# C128_U36_1MB_V2.net
KiCad netlist of a schematic drawn in EAGLE
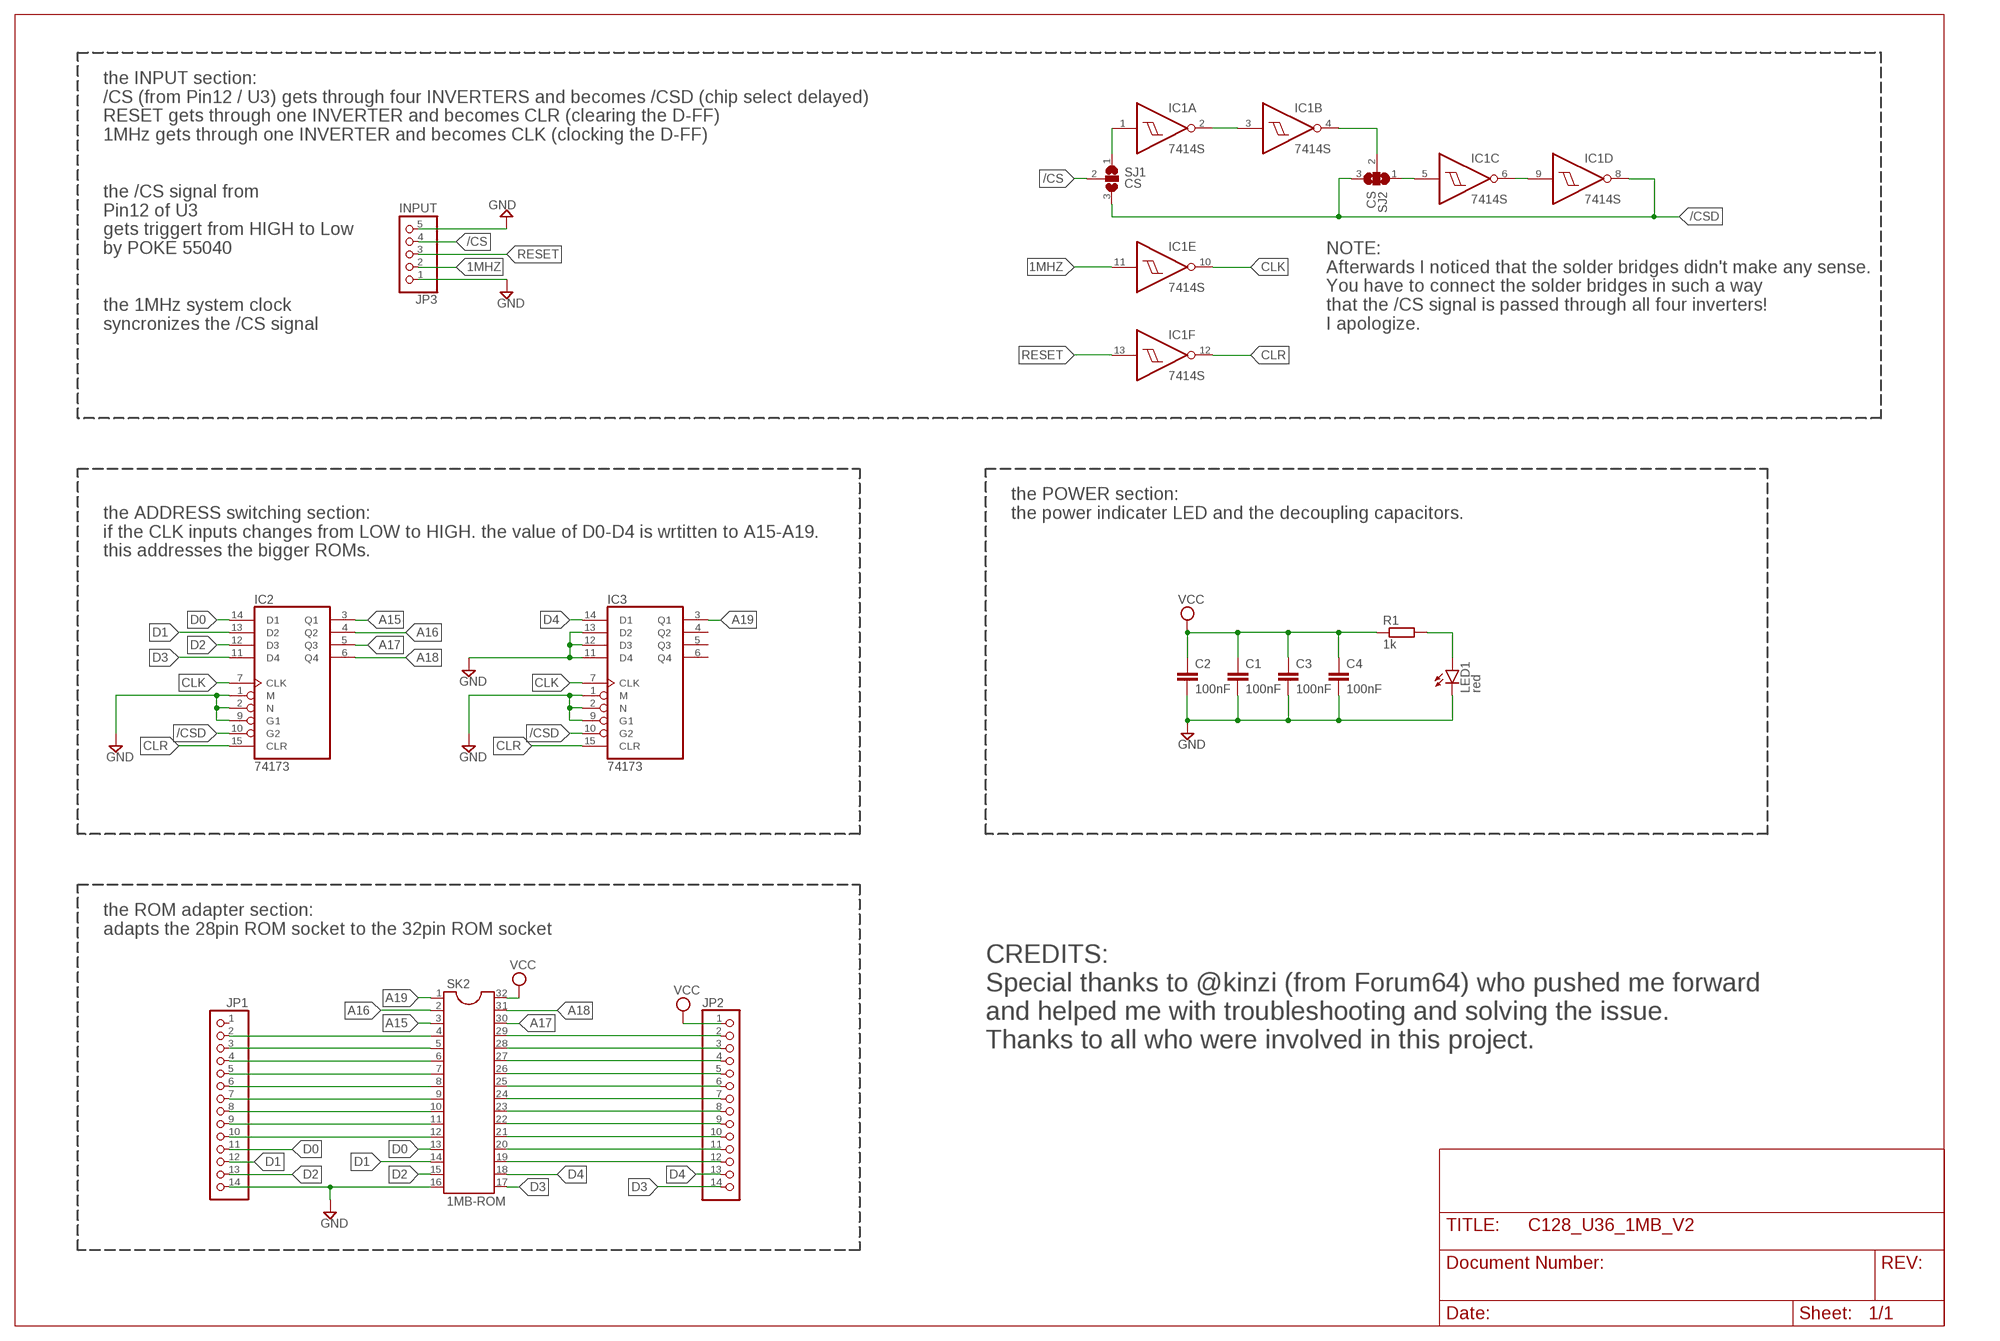
[diagram p0: schematic, sheet 1]

(export (version "E")
  (design (tool "Eeschema 10.0.6"))
  (components
    (comp (ref "C1")
      (value "100nF")
      (footprint "eagle-import:C0603K")
      (libsource (lib "eagle-import") (part "C-EUC0603K"))
    )
    (comp (ref "C2")
      (value "100nF")
      (footprint "eagle-import:C0603K")
      (libsource (lib "eagle-import") (part "C-EUC0603K"))
    )
    (comp (ref "C3")
      (value "100nF")
      (footprint "eagle-import:C0603K")
      (libsource (lib "eagle-import") (part "C-EUC0603K"))
    )
    (comp (ref "C4")
      (value "100nF")
      (footprint "eagle-import:C0603K")
      (libsource (lib "eagle-import") (part "C-EUC0603K"))
    )
    (comp (ref "IC1")
      (value "7414S")
      (footprint "eagle-import:SO14_DET")
      (libsource (lib "eagle-import") (part "7414SMALL"))
    )
    (comp (ref "IC2")
      (value "74173")
      (footprint "eagle-import:SO16_DET")
      (libsource (lib "eagle-import") (part "74173"))
    )
    (comp (ref "IC3")
      (value "74173")
      (footprint "eagle-import:SO16_DET")
      (fields (field (name "SPICEPREFIX") "X"))
      (libsource (lib "eagle-import") (part "74173"))
    )
    (comp (ref "JP1")
      (value "PINHD-1X14")
      (footprint "eagle-import:1X14")
      (libsource (lib "eagle-import") (part "PINHD-1X14"))
    )
    (comp (ref "JP2")
      (value "PINHD-1X14")
      (footprint "eagle-import:1X14")
      (libsource (lib "eagle-import") (part "PINHD-1X14"))
    )
    (comp (ref "JP3")
      (value "INPUT")
      (footprint "eagle-import:1X05_90")
      (libsource (lib "eagle-import") (part "PINHD-1X5/90"))
    )
    (comp (ref "LED1")
      (value "red")
      (footprint "eagle-import:CHIPLED_0603")
      (libsource (lib "eagle-import") (part "LEDCHIPLED_0603"))
    )
    (comp (ref "R1")
      (value "1k")
      (footprint "eagle-import:R0603")
      (libsource (lib "eagle-import") (part "R-EU_R0603"))
    )
    (comp (ref "SJ1")
      (value "CS")
      (footprint "eagle-import:SJ_2")
      (libsource (lib "eagle-import") (part "SJ2W"))
    )
    (comp (ref "SJ2")
      (value "CS")
      (footprint "eagle-import:SJ_2")
      (libsource (lib "eagle-import") (part "SJ2W"))
    )
    (comp (ref "SK2")
      (value "1MB-ROM")
      (footprint "eagle-import:DIL32")
      (libsource (lib "eagle-import") (part "DIL32"))
    )
  )
  (nets
    (net (code "1") (name "1MHZ") (class "Default")
      (node (ref "IC1") (pin "11") (pinfunction "I_11") (pintype "input"))
      (node (ref "JP3") (pin "2") (pinfunction "2_2") (pintype "passive"))
    )
    (net (code "2") (name "A15") (class "Default")
      (node (ref "IC2") (pin "3") (pinfunction "Q1_3") (pintype "tri_state"))
      (node (ref "SK2") (pin "3") (pinfunction "3_3") (pintype "passive"))
    )
    (net (code "3") (name "A16") (class "Default")
      (node (ref "IC2") (pin "4") (pinfunction "Q2_4") (pintype "tri_state"))
      (node (ref "SK2") (pin "2") (pinfunction "2_2") (pintype "passive"))
    )
    (net (code "4") (name "A17") (class "Default")
      (node (ref "IC2") (pin "5") (pinfunction "Q3_5") (pintype "tri_state"))
      (node (ref "SK2") (pin "30") (pinfunction "30_30") (pintype "passive"))
    )
    (net (code "5") (name "A18") (class "Default")
      (node (ref "IC2") (pin "6") (pinfunction "Q4_6") (pintype "tri_state"))
      (node (ref "SK2") (pin "31") (pinfunction "31_31") (pintype "passive"))
    )
    (net (code "6") (name "A19") (class "Default")
      (node (ref "IC3") (pin "3") (pinfunction "Q1_3") (pintype "tri_state"))
      (node (ref "SK2") (pin "1") (pinfunction "1_1") (pintype "passive"))
    )
    (net (code "7") (name "CLK") (class "Default")
      (node (ref "IC1") (pin "10") (pinfunction "O_10") (pintype "output"))
      (node (ref "IC2") (pin "7") (pinfunction "CLK_7") (pintype "input"))
      (node (ref "IC3") (pin "7") (pinfunction "CLK_7") (pintype "input"))
    )
    (net (code "8") (name "CLR") (class "Default")
      (node (ref "IC1") (pin "12") (pinfunction "O_12") (pintype "output"))
      (node (ref "IC2") (pin "15") (pinfunction "CLR_15") (pintype "input"))
      (node (ref "IC3") (pin "15") (pinfunction "CLR_15") (pintype "input"))
    )
    (net (code "9") (name "D0") (class "Default")
      (node (ref "IC2") (pin "14") (pinfunction "D1_14") (pintype "input"))
      (node (ref "JP1") (pin "11") (pinfunction "11_11") (pintype "passive"))
      (node (ref "SK2") (pin "13") (pinfunction "13_13") (pintype "passive"))
    )
    (net (code "10") (name "D1") (class "Default")
      (node (ref "IC2") (pin "13") (pinfunction "D2_13") (pintype "input"))
      (node (ref "JP1") (pin "12") (pinfunction "12_12") (pintype "passive"))
      (node (ref "SK2") (pin "14") (pinfunction "14_14") (pintype "passive"))
    )
    (net (code "11") (name "D2") (class "Default")
      (node (ref "IC2") (pin "12") (pinfunction "D3_12") (pintype "input"))
      (node (ref "JP1") (pin "13") (pinfunction "13_13") (pintype "passive"))
      (node (ref "SK2") (pin "15") (pinfunction "15_15") (pintype "passive"))
    )
    (net (code "12") (name "D3") (class "Default")
      (node (ref "IC2") (pin "11") (pinfunction "D4_11") (pintype "input"))
      (node (ref "JP2") (pin "14") (pinfunction "14_14") (pintype "passive"))
      (node (ref "SK2") (pin "17") (pinfunction "17_17") (pintype "passive"))
    )
    (net (code "13") (name "D4") (class "Default")
      (node (ref "IC3") (pin "14") (pinfunction "D1_14") (pintype "input"))
      (node (ref "JP2") (pin "13") (pinfunction "13_13") (pintype "passive"))
      (node (ref "SK2") (pin "18") (pinfunction "18_18") (pintype "passive"))
    )
    (net (code "14") (name "GND") (class "Default")
      (node (ref "C1") (pin "2") (pinfunction "2_2") (pintype "passive"))
      (node (ref "C2") (pin "2") (pinfunction "2_2") (pintype "passive"))
      (node (ref "C3") (pin "2") (pinfunction "2_2") (pintype "passive"))
      (node (ref "C4") (pin "2") (pinfunction "2_2") (pintype "passive"))
      (node (ref "IC2") (pin "1") (pinfunction "M_1") (pintype "input"))
      (node (ref "IC2") (pin "2") (pinfunction "N_2") (pintype "input"))
      (node (ref "IC2") (pin "9") (pinfunction "G1_9") (pintype "input"))
      (node (ref "IC3") (pin "1") (pinfunction "M_1") (pintype "input"))
      (node (ref "IC3") (pin "11") (pinfunction "D4_11") (pintype "input"))
      (node (ref "IC3") (pin "12") (pinfunction "D3_12") (pintype "input"))
      (node (ref "IC3") (pin "13") (pinfunction "D2_13") (pintype "input"))
      (node (ref "IC3") (pin "2") (pinfunction "N_2") (pintype "input"))
      (node (ref "IC3") (pin "9") (pinfunction "G1_9") (pintype "input"))
      (node (ref "JP1") (pin "14") (pinfunction "14_14") (pintype "passive"))
      (node (ref "JP3") (pin "1") (pinfunction "1_1") (pintype "passive"))
      (node (ref "JP3") (pin "5") (pinfunction "5_5") (pintype "passive"))
      (node (ref "LED1") (pin "C") (pinfunction "C_C") (pintype "passive"))
      (node (ref "SK2") (pin "16") (pinfunction "16_16") (pintype "passive"))
    )
    (net (code "15") (name "Net-(IC1A-I)") (class "Default")
      (node (ref "IC1") (pin "1") (pinfunction "I_1") (pintype "input"))
      (node (ref "SJ1") (pin "1") (pinfunction "1_1") (pintype "passive"))
    )
    (net (code "16") (name "Net-(IC1A-O)") (class "Default")
      (node (ref "IC1") (pin "2") (pinfunction "O_2") (pintype "output"))
      (node (ref "IC1") (pin "3") (pinfunction "I_3") (pintype "input"))
    )
    (net (code "17") (name "Net-(IC1B-O)") (class "Default")
      (node (ref "IC1") (pin "4") (pinfunction "O_4") (pintype "output"))
      (node (ref "SJ2") (pin "2") (pinfunction "2_2") (pintype "passive"))
    )
    (net (code "18") (name "Net-(IC1C-I)") (class "Default")
      (node (ref "IC1") (pin "5") (pinfunction "I_5") (pintype "input"))
      (node (ref "SJ2") (pin "1") (pinfunction "1_1") (pintype "passive"))
    )
    (net (code "19") (name "Net-(IC1C-O)") (class "Default")
      (node (ref "IC1") (pin "6") (pinfunction "O_6") (pintype "output"))
      (node (ref "IC1") (pin "9") (pinfunction "I_9") (pintype "input"))
    )
    (net (code "20") (name "Net-(JP1-Pad2)") (class "Default")
      (node (ref "JP1") (pin "2") (pinfunction "2_2") (pintype "passive"))
      (node (ref "SK2") (pin "4") (pinfunction "4_4") (pintype "passive"))
    )
    (net (code "21") (name "Net-(JP1-Pad3)") (class "Default")
      (node (ref "JP1") (pin "3") (pinfunction "3_3") (pintype "passive"))
      (node (ref "SK2") (pin "5") (pinfunction "5_5") (pintype "passive"))
    )
    (net (code "22") (name "Net-(JP1-Pad4)") (class "Default")
      (node (ref "JP1") (pin "4") (pinfunction "4_4") (pintype "passive"))
      (node (ref "SK2") (pin "6") (pinfunction "6_6") (pintype "passive"))
    )
    (net (code "23") (name "Net-(JP1-Pad5)") (class "Default")
      (node (ref "JP1") (pin "5") (pinfunction "5_5") (pintype "passive"))
      (node (ref "SK2") (pin "7") (pinfunction "7_7") (pintype "passive"))
    )
    (net (code "24") (name "Net-(JP1-Pad6)") (class "Default")
      (node (ref "JP1") (pin "6") (pinfunction "6_6") (pintype "passive"))
      (node (ref "SK2") (pin "8") (pinfunction "8_8") (pintype "passive"))
    )
    (net (code "25") (name "Net-(JP1-Pad7)") (class "Default")
      (node (ref "JP1") (pin "7") (pinfunction "7_7") (pintype "passive"))
      (node (ref "SK2") (pin "9") (pinfunction "9_9") (pintype "passive"))
    )
    (net (code "26") (name "Net-(JP1-Pad8)") (class "Default")
      (node (ref "JP1") (pin "8") (pinfunction "8_8") (pintype "passive"))
      (node (ref "SK2") (pin "10") (pinfunction "10_10") (pintype "passive"))
    )
    (net (code "27") (name "Net-(JP1-Pad9)") (class "Default")
      (node (ref "JP1") (pin "9") (pinfunction "9_9") (pintype "passive"))
      (node (ref "SK2") (pin "11") (pinfunction "11_11") (pintype "passive"))
    )
    (net (code "28") (name "Net-(JP1-Pad10)") (class "Default")
      (node (ref "JP1") (pin "10") (pinfunction "10_10") (pintype "passive"))
      (node (ref "SK2") (pin "12") (pinfunction "12_12") (pintype "passive"))
    )
    (net (code "29") (name "Net-(JP2-Pad2)") (class "Default")
      (node (ref "JP2") (pin "2") (pinfunction "2_2") (pintype "passive"))
      (node (ref "SK2") (pin "29") (pinfunction "29_29") (pintype "passive"))
    )
    (net (code "30") (name "Net-(JP2-Pad3)") (class "Default")
      (node (ref "JP2") (pin "3") (pinfunction "3_3") (pintype "passive"))
      (node (ref "SK2") (pin "28") (pinfunction "28_28") (pintype "passive"))
    )
    (net (code "31") (name "Net-(JP2-Pad4)") (class "Default")
      (node (ref "JP2") (pin "4") (pinfunction "4_4") (pintype "passive"))
      (node (ref "SK2") (pin "27") (pinfunction "27_27") (pintype "passive"))
    )
    (net (code "32") (name "Net-(JP2-Pad5)") (class "Default")
      (node (ref "JP2") (pin "5") (pinfunction "5_5") (pintype "passive"))
      (node (ref "SK2") (pin "26") (pinfunction "26_26") (pintype "passive"))
    )
    (net (code "33") (name "Net-(JP2-Pad6)") (class "Default")
      (node (ref "JP2") (pin "6") (pinfunction "6_6") (pintype "passive"))
      (node (ref "SK2") (pin "25") (pinfunction "25_25") (pintype "passive"))
    )
    (net (code "34") (name "Net-(JP2-Pad7)") (class "Default")
      (node (ref "JP2") (pin "7") (pinfunction "7_7") (pintype "passive"))
      (node (ref "SK2") (pin "24") (pinfunction "24_24") (pintype "passive"))
    )
    (net (code "35") (name "Net-(JP2-Pad8)") (class "Default")
      (node (ref "JP2") (pin "8") (pinfunction "8_8") (pintype "passive"))
      (node (ref "SK2") (pin "23") (pinfunction "23_23") (pintype "passive"))
    )
    (net (code "36") (name "Net-(JP2-Pad9)") (class "Default")
      (node (ref "JP2") (pin "9") (pinfunction "9_9") (pintype "passive"))
      (node (ref "SK2") (pin "22") (pinfunction "22_22") (pintype "passive"))
    )
    (net (code "37") (name "Net-(JP2-Pad10)") (class "Default")
      (node (ref "JP2") (pin "10") (pinfunction "10_10") (pintype "passive"))
      (node (ref "SK2") (pin "21") (pinfunction "21_21") (pintype "passive"))
    )
    (net (code "38") (name "Net-(JP2-Pad11)") (class "Default")
      (node (ref "JP2") (pin "11") (pinfunction "11_11") (pintype "passive"))
      (node (ref "SK2") (pin "20") (pinfunction "20_20") (pintype "passive"))
    )
    (net (code "39") (name "Net-(JP2-Pad12)") (class "Default")
      (node (ref "JP2") (pin "12") (pinfunction "12_12") (pintype "passive"))
      (node (ref "SK2") (pin "19") (pinfunction "19_19") (pintype "passive"))
    )
    (net (code "40") (name "Net-(LED1-PadA)") (class "Default")
      (node (ref "LED1") (pin "A") (pinfunction "A_A") (pintype "passive"))
      (node (ref "R1") (pin "2") (pinfunction "2_2") (pintype "passive"))
    )
    (net (code "41") (name "RESET") (class "Default")
      (node (ref "IC1") (pin "13") (pinfunction "I_13") (pintype "input"))
      (node (ref "JP3") (pin "3") (pinfunction "3_3") (pintype "passive"))
    )
    (net (code "42") (name "VCC") (class "Default")
      (node (ref "C1") (pin "1") (pinfunction "1_1") (pintype "passive"))
      (node (ref "C2") (pin "1") (pinfunction "1_1") (pintype "passive"))
      (node (ref "C3") (pin "1") (pinfunction "1_1") (pintype "passive"))
      (node (ref "C4") (pin "1") (pinfunction "1_1") (pintype "passive"))
      (node (ref "JP2") (pin "1") (pinfunction "1_1") (pintype "passive"))
      (node (ref "R1") (pin "1") (pinfunction "1_1") (pintype "passive"))
      (node (ref "SK2") (pin "32") (pinfunction "32_32") (pintype "passive"))
    )
    (net (code "43") (name "unconnected-(IC3A-Q2-Pad4)") (class "Default")
      (node (ref "IC3") (pin "4") (pinfunction "Q2_4") (pintype "tri_state"))
    )
    (net (code "44") (name "unconnected-(IC3A-Q3-Pad5)") (class "Default")
      (node (ref "IC3") (pin "5") (pinfunction "Q3_5") (pintype "tri_state"))
    )
    (net (code "45") (name "unconnected-(IC3A-Q4-Pad6)") (class "Default")
      (node (ref "IC3") (pin "6") (pinfunction "Q4_6") (pintype "tri_state"))
    )
    (net (code "46") (name "unconnected-(JP1-Pad1)") (class "Default")
      (node (ref "JP1") (pin "1") (pinfunction "1_1") (pintype "passive"))
    )
    (net (code "47") (name "{slash}CS") (class "Default")
      (node (ref "JP3") (pin "4") (pinfunction "4_4") (pintype "passive"))
      (node (ref "SJ1") (pin "2") (pinfunction "2_2") (pintype "passive"))
    )
    (net (code "48") (name "{slash}CSD") (class "Default")
      (node (ref "IC1") (pin "8") (pinfunction "O_8") (pintype "output"))
      (node (ref "IC2") (pin "10") (pinfunction "G2_10") (pintype "input"))
      (node (ref "IC3") (pin "10") (pinfunction "G2_10") (pintype "input"))
      (node (ref "SJ1") (pin "3") (pinfunction "3_3") (pintype "passive"))
      (node (ref "SJ2") (pin "3") (pinfunction "3_3") (pintype "passive"))
    )
  )
)
